# SCH_usbhubpcb2_2024-06-19.net
KiCad netlist of a schematic drawn in EasyEDA
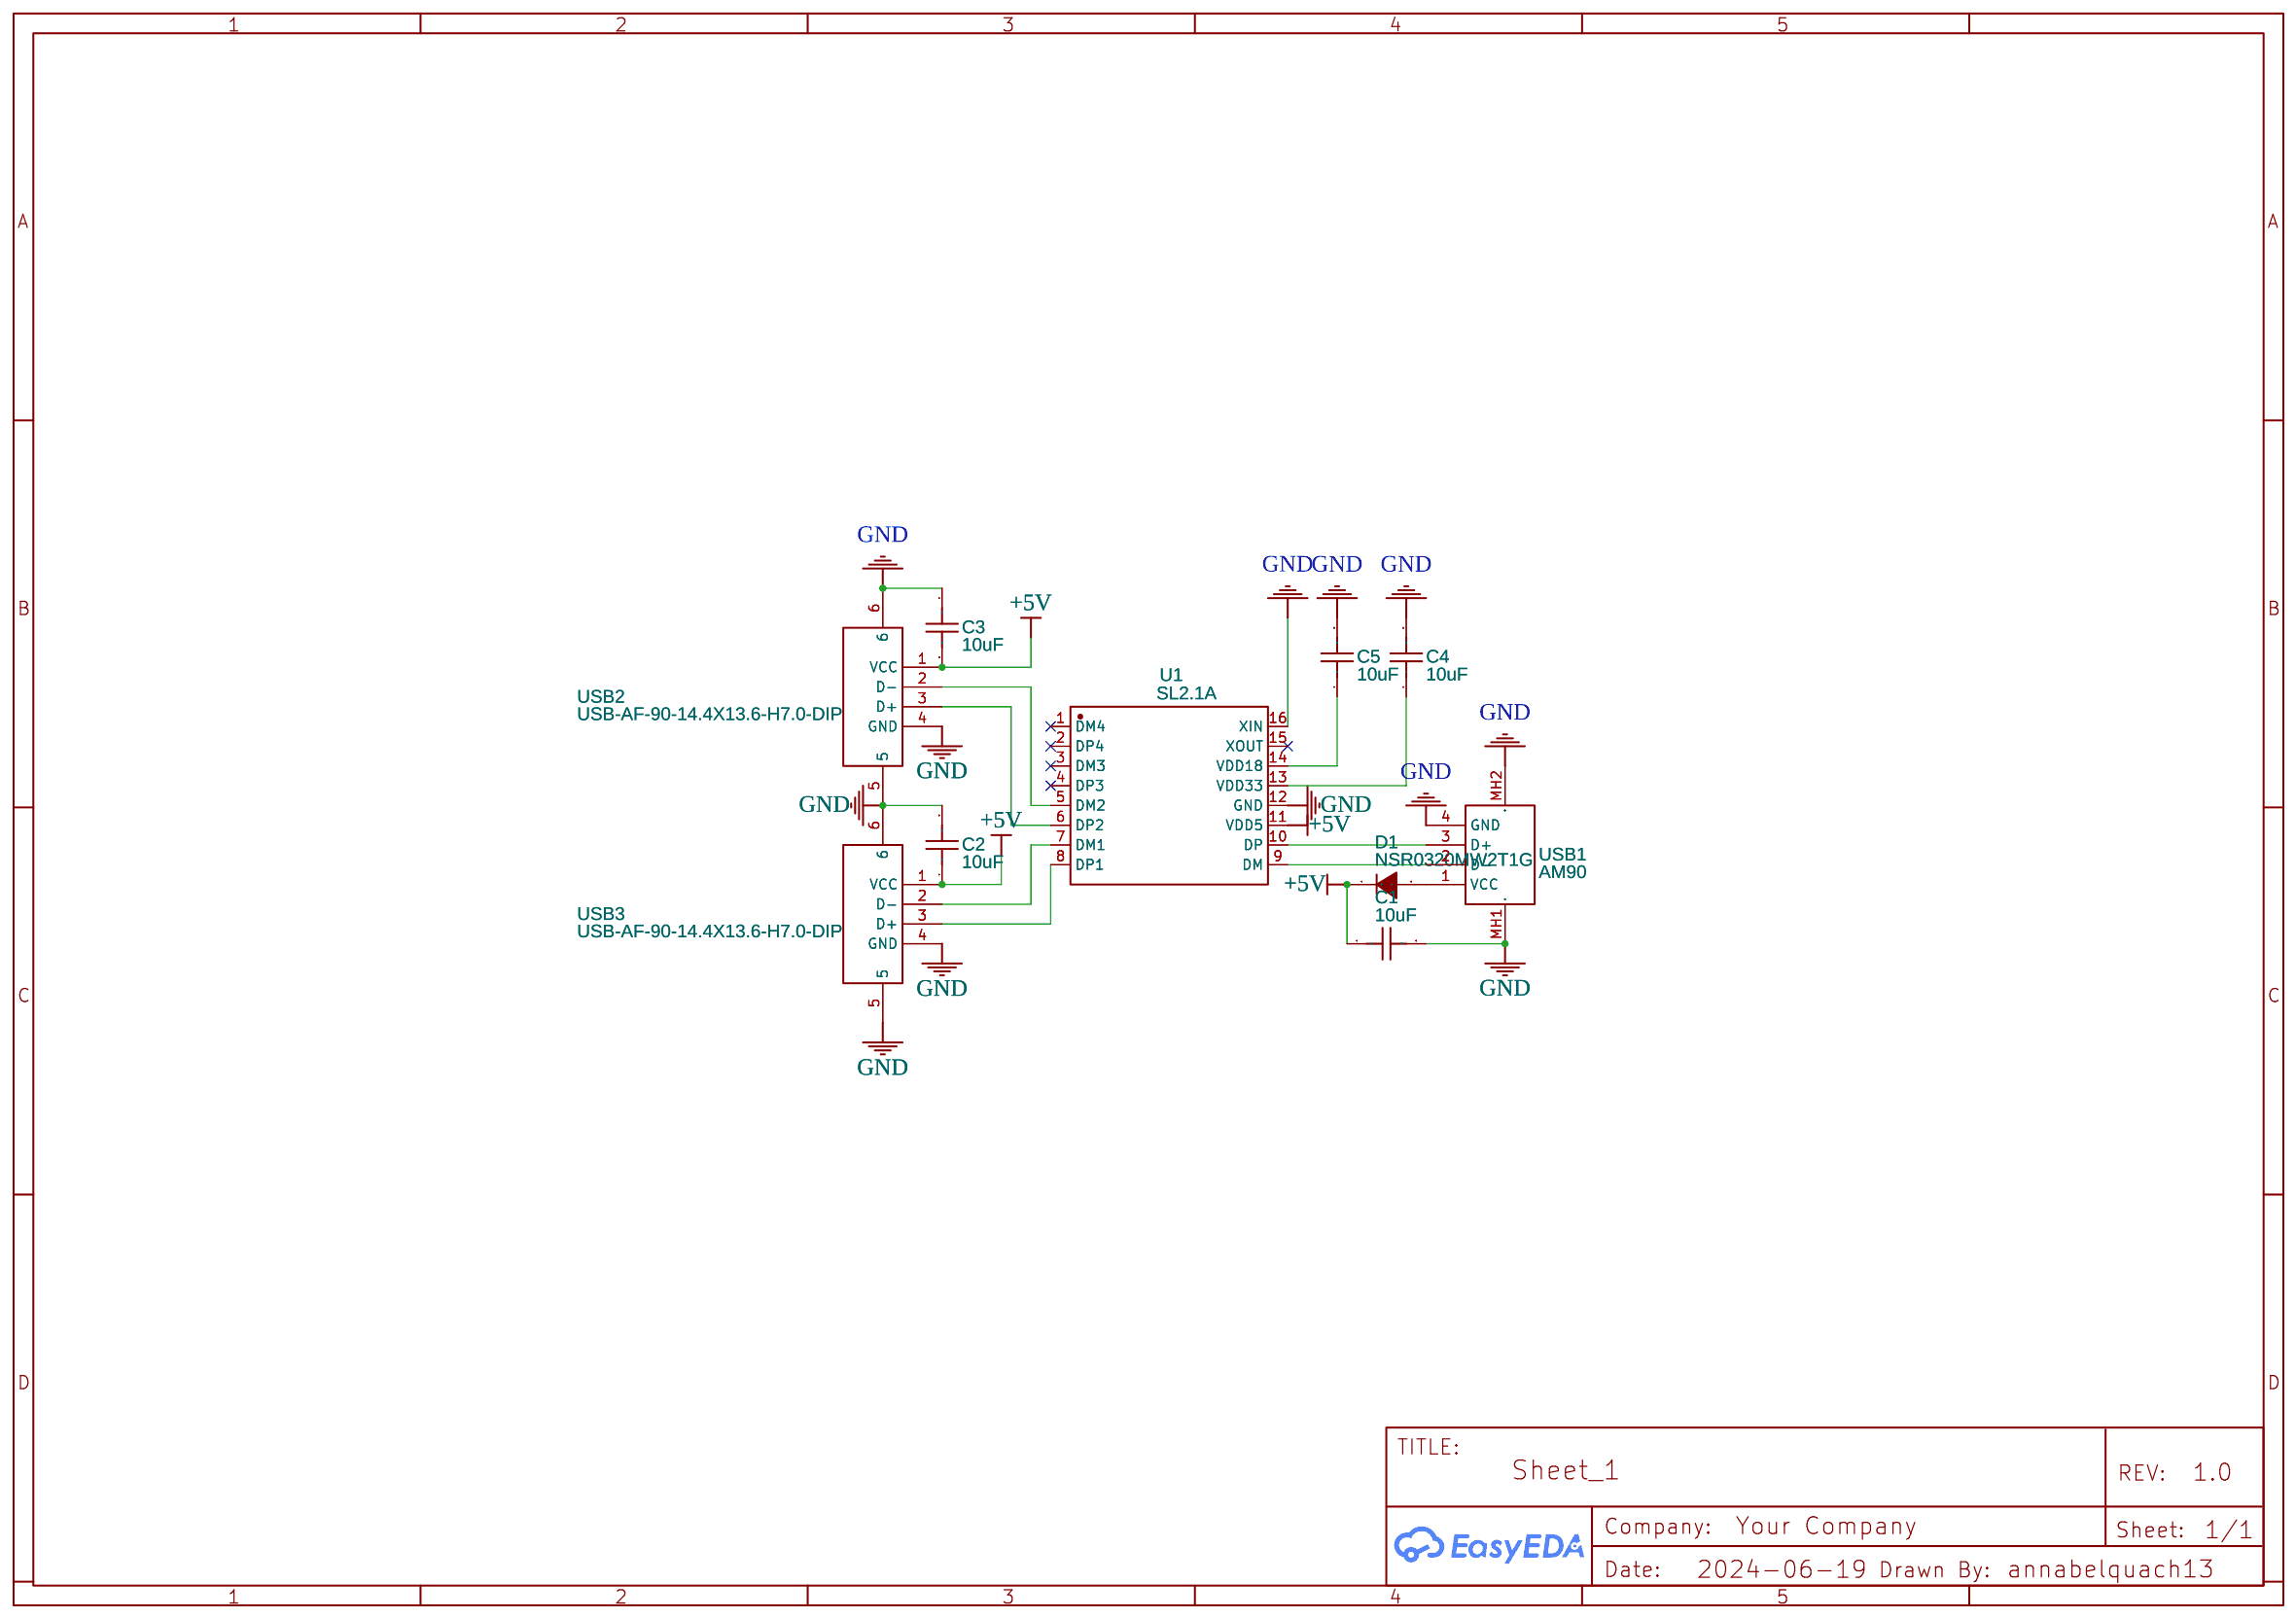
[diagram p0: schematic sheet]

(export (version "E")
  (design (tool "Eeschema 10.0.6"))
  (components
    (comp (ref "C1")
      (value "10uF")
      (fields
        (field (name "Manufacturer Part") "CL10A106KP8NNNC")
        (field (name "Manufacturer") "SAMSUNG(三星)")
      )
      (libsource (lib "") (part "CL10A106KP8NNNC"))
    )
    (comp (ref "C2")
      (value "10uF")
      (fields
        (field (name "Manufacturer Part") "CL10A106KP8NNNC")
        (field (name "Manufacturer") "SAMSUNG(三星)")
      )
      (libsource (lib "") (part "CL10A106KP8NNNC_1"))
    )
    (comp (ref "C3")
      (value "10uF")
      (fields
        (field (name "Manufacturer Part") "CL10A106KP8NNNC")
        (field (name "Manufacturer") "SAMSUNG(三星)")
      )
      (libsource (lib "") (part "CL10A106KP8NNNC_2"))
    )
    (comp (ref "C4")
      (value "10uF")
      (fields
        (field (name "Manufacturer Part") "CL10A106KP8NNNC")
        (field (name "Manufacturer") "SAMSUNG(三星)")
      )
      (libsource (lib "") (part "CL10A106KP8NNNC_1"))
    )
    (comp (ref "C5")
      (value "10uF")
      (fields
        (field (name "Manufacturer Part") "CL10A106KP8NNNC")
        (field (name "Manufacturer") "SAMSUNG(三星)")
      )
      (libsource (lib "") (part "CL10A106KP8NNNC_1"))
    )
    (comp (ref "D1")
      (value "NSR0320MW2T1G")
      (fields (field (name "Manufacturer") "onsemi(安森美)"))
      (libsource (lib "") (part "NSR0320MW2T1G"))
    )
    (comp (ref "U1")
      (value "SL2.1A")
      (fields (field (name "Manufacturer") "CoreChips(和芯润德)"))
      (libsource (lib "") (part "SL2.1A"))
    )
    (comp (ref "USB1")
      (value "AM90")
      (fields (field (name "Manufacturer") "SHOU HAN(首韩)"))
      (libsource (lib "") (part "AM90"))
    )
    (comp (ref "USB2")
      (value "USB-AF-90-14.4X13.6-H7.0-DIP")
      (fields (field (name "Manufacturer Part") "903-131A1011D10100") (field (name "Manufacturer") "精拓金"))
      (libsource (lib "") (part "USB-AF-90-14.4X13.6-H7.0-DIP"))
    )
    (comp (ref "USB3")
      (value "USB-AF-90-14.4X13.6-H7.0-DIP")
      (fields (field (name "Manufacturer Part") "903-131A1011D10100") (field (name "Manufacturer") "精拓金"))
      (libsource (lib "") (part "USB-AF-90-14.4X13.6-H7.0-DIP"))
    )
  )
  (nets
    (net (code "1") (name "+5V") (class "Default")
      (node (ref "C1") (pin "1") (pinfunction "1_1") (pintype "unspecified"))
      (node (ref "C2") (pin "1") (pinfunction "1_1") (pintype "unspecified"))
      (node (ref "C3") (pin "2") (pinfunction "2_2") (pintype "unspecified"))
      (node (ref "D1") (pin "1") (pinfunction "C_1") (pintype "unspecified"))
      (node (ref "U1") (pin "11") (pinfunction "VDD5_11") (pintype "unspecified"))
      (node (ref "USB2") (pin "1") (pinfunction "VCC_1") (pintype "unspecified"))
      (node (ref "USB3") (pin "1") (pinfunction "VCC_1") (pintype "unspecified"))
    )
    (net (code "2") (name "GND") (class "Default")
      (node (ref "C1") (pin "2") (pinfunction "2_2") (pintype "unspecified"))
      (node (ref "C2") (pin "2") (pinfunction "2_2") (pintype "unspecified"))
      (node (ref "C3") (pin "1") (pinfunction "1_1") (pintype "unspecified"))
      (node (ref "C4") (pin "2") (pinfunction "2_2") (pintype "unspecified"))
      (node (ref "C5") (pin "2") (pinfunction "2_2") (pintype "unspecified"))
      (node (ref "U1") (pin "12") (pinfunction "GND_12") (pintype "unspecified"))
      (node (ref "U1") (pin "16") (pinfunction "XIN_16") (pintype "unspecified"))
      (node (ref "USB1") (pin "4") (pinfunction "GND_4") (pintype "input"))
      (node (ref "USB1") (pin "MH1") (pinfunction "MH1_MH1") (pintype "unspecified"))
      (node (ref "USB1") (pin "MH2") (pinfunction "MH2_MH2") (pintype "unspecified"))
      (node (ref "USB2") (pin "4") (pinfunction "GND_4") (pintype "unspecified"))
      (node (ref "USB2") (pin "5") (pinfunction "5_5") (pintype "unspecified"))
      (node (ref "USB2") (pin "6") (pinfunction "6_6") (pintype "unspecified"))
      (node (ref "USB3") (pin "4") (pinfunction "GND_4") (pintype "unspecified"))
      (node (ref "USB3") (pin "5") (pinfunction "5_5") (pintype "unspecified"))
      (node (ref "USB3") (pin "6") (pinfunction "6_6") (pintype "unspecified"))
    )
    (net (code "3") (name "Net-(D1-A)") (class "Default")
      (node (ref "D1") (pin "2") (pinfunction "A_2") (pintype "unspecified"))
      (node (ref "USB1") (pin "1") (pinfunction "VCC_1") (pintype "input"))
    )
    (net (code "4") (name "Net-(U1-DM)") (class "Default")
      (node (ref "U1") (pin "9") (pinfunction "DM_9") (pintype "unspecified"))
      (node (ref "USB1") (pin "2") (pinfunction "D-_2") (pintype "input"))
    )
    (net (code "5") (name "Net-(U1-DM1)") (class "Default")
      (node (ref "U1") (pin "7") (pinfunction "DM1_7") (pintype "unspecified"))
      (node (ref "USB3") (pin "2") (pinfunction "D-_2") (pintype "unspecified"))
    )
    (net (code "6") (name "Net-(U1-DM2)") (class "Default")
      (node (ref "U1") (pin "5") (pinfunction "DM2_5") (pintype "unspecified"))
      (node (ref "USB2") (pin "2") (pinfunction "D-_2") (pintype "unspecified"))
    )
    (net (code "7") (name "Net-(U1-DP)") (class "Default")
      (node (ref "U1") (pin "10") (pinfunction "DP_10") (pintype "unspecified"))
      (node (ref "USB1") (pin "3") (pinfunction "D+_3") (pintype "input"))
    )
    (net (code "8") (name "Net-(U1-DP1)") (class "Default")
      (node (ref "U1") (pin "8") (pinfunction "DP1_8") (pintype "unspecified"))
      (node (ref "USB3") (pin "3") (pinfunction "D+_3") (pintype "unspecified"))
    )
    (net (code "9") (name "Net-(U1-DP2)") (class "Default")
      (node (ref "U1") (pin "6") (pinfunction "DP2_6") (pintype "unspecified"))
      (node (ref "USB2") (pin "3") (pinfunction "D+_3") (pintype "unspecified"))
    )
    (net (code "10") (name "Net-(U1-VDD18)") (class "Default")
      (node (ref "C5") (pin "1") (pinfunction "1_1") (pintype "unspecified"))
      (node (ref "U1") (pin "14") (pinfunction "VDD18_14") (pintype "unspecified"))
    )
    (net (code "11") (name "Net-(U1-VDD33)") (class "Default")
      (node (ref "C4") (pin "1") (pinfunction "1_1") (pintype "unspecified"))
      (node (ref "U1") (pin "13") (pinfunction "VDD33_13") (pintype "unspecified"))
    )
    (net (code "12") (name "unconnected-(U1-DM3-Pad3)") (class "Default")
      (node (ref "U1") (pin "3") (pinfunction "DM3_3") (pintype "unspecified+no_connect"))
    )
    (net (code "13") (name "unconnected-(U1-DM4-Pad1)") (class "Default")
      (node (ref "U1") (pin "1") (pinfunction "DM4_1") (pintype "unspecified+no_connect"))
    )
    (net (code "14") (name "unconnected-(U1-DP3-Pad4)") (class "Default")
      (node (ref "U1") (pin "4") (pinfunction "DP3_4") (pintype "unspecified+no_connect"))
    )
    (net (code "15") (name "unconnected-(U1-DP4-Pad2)") (class "Default")
      (node (ref "U1") (pin "2") (pinfunction "DP4_2") (pintype "unspecified+no_connect"))
    )
    (net (code "16") (name "unconnected-(U1-XOUT-Pad15)") (class "Default")
      (node (ref "U1") (pin "15") (pinfunction "XOUT_15") (pintype "unspecified+no_connect"))
    )
  )
)
